# 2312_SchemaBloc.net
KiCad netlist of a schematic drawn in Altium Designer
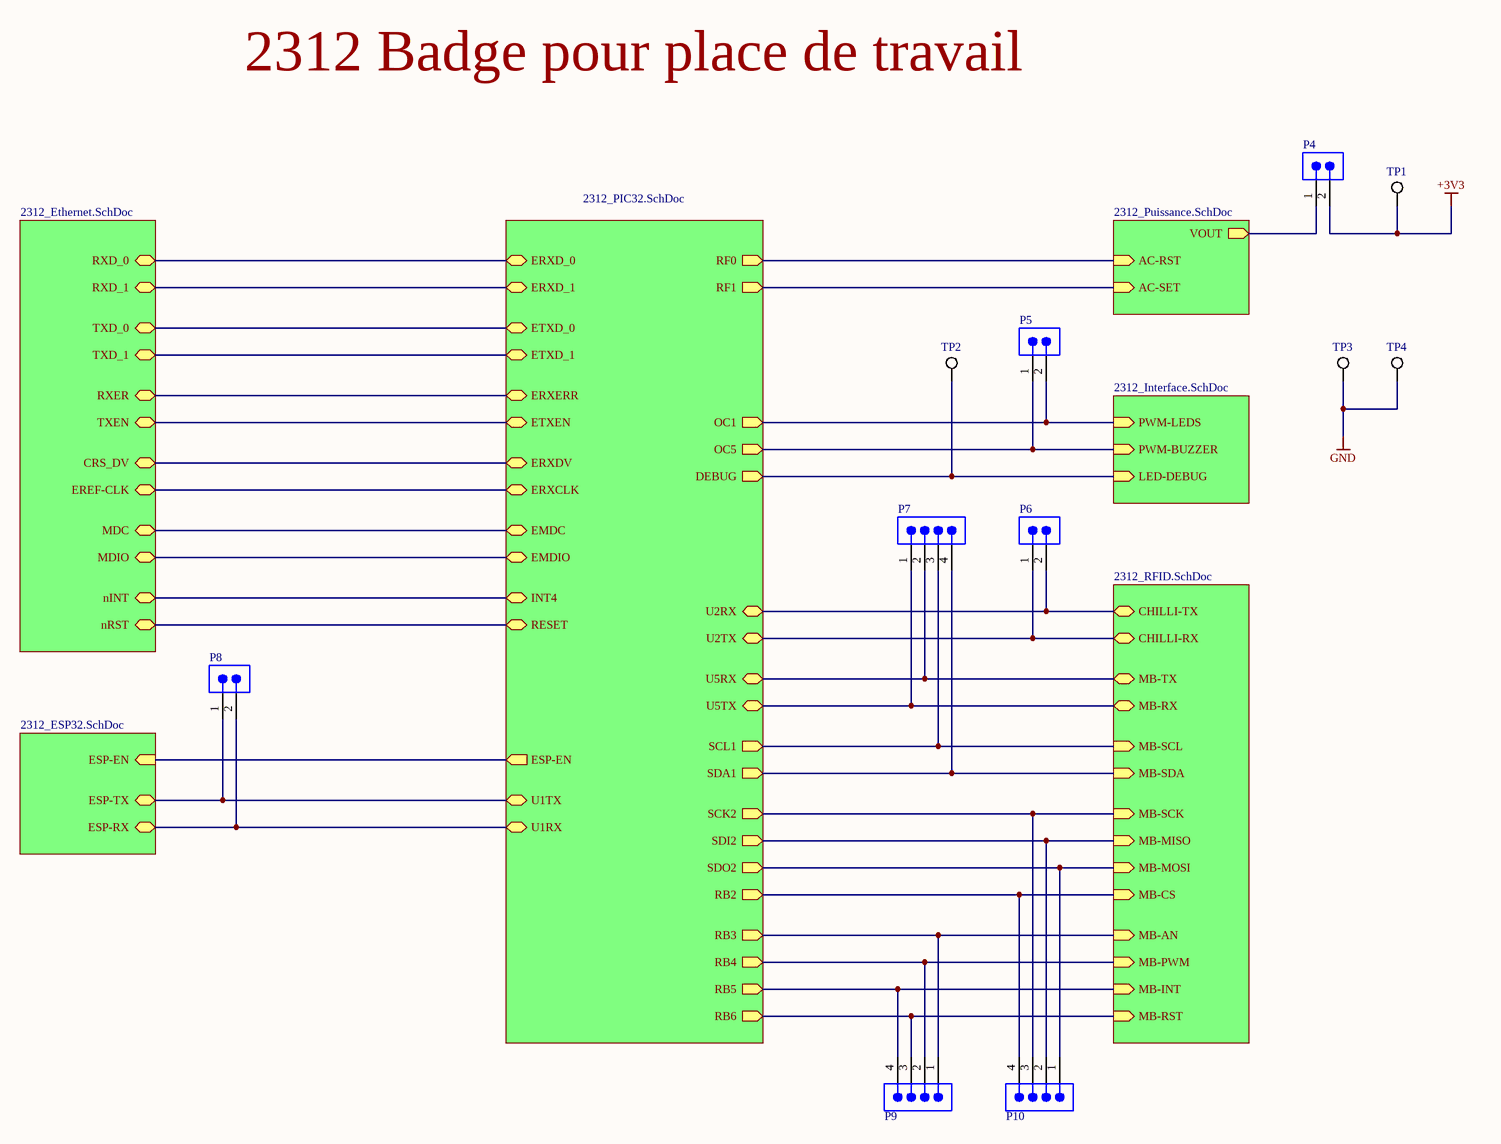
[diagram p0: 2312_SchemaBloc.SchDoc]

(export (version "E")
  (design (tool "Eeschema 10.0.6"))
  (components
    (comp (ref "P4")
      (value "61300211121")
      (footprint "61300211121")
      (description "WR-PHD Pin Header, THT, Vertical, pitch 2.54mm, 1 Row, 2P")
      (fields (field (name "MANUFACTURER") "Wurth Elektronik"))
      (libsource (lib "WR-PHD") (part "61300211121"))
    )
    (comp (ref "P5")
      (value "61300211121")
      (footprint "61300211121")
      (description "WR-PHD Pin Header, THT, Vertical, pitch 2.54mm, 1 Row, 2P")
      (fields (field (name "MANUFACTURER") "Wurth Elektronik"))
      (libsource (lib "WR-PHD") (part "61300211121"))
    )
    (comp (ref "P6")
      (value "61300211121")
      (footprint "61300211121")
      (description "WR-PHD Pin Header, THT, Vertical, pitch 2.54mm, 1 Row, 2P")
      (fields (field (name "MANUFACTURER") "Wurth Elektronik"))
      (libsource (lib "WR-PHD") (part "61300211121"))
    )
    (comp (ref "P7")
      (value "61300411121")
      (footprint "61300411121")
      (description "WR-PHD Pin Header, THT, Vertical, pitch 2.54mm, 1 Row, 4P")
      (fields (field (name "MANUFACTURER") "Wurth Elektronik"))
      (libsource (lib "WR-PHD") (part "61300411121"))
    )
    (comp (ref "P8")
      (value "61300211121")
      (footprint "61300211121")
      (description "WR-PHD Pin Header, THT, Vertical, pitch 2.54mm, 1 Row, 2P")
      (fields (field (name "MANUFACTURER") "Wurth Elektronik"))
      (libsource (lib "WR-PHD") (part "61300211121"))
    )
    (comp (ref "P9")
      (value "61300411121")
      (footprint "61300411121")
      (description "WR-PHD Pin Header, THT, Vertical, pitch 2.54mm, 1 Row, 4P")
      (fields (field (name "MANUFACTURER") "Wurth Elektronik"))
      (libsource (lib "WR-PHD") (part "61300411121"))
    )
    (comp (ref "P10")
      (value "61300411121")
      (footprint "61300411121")
      (description "WR-PHD Pin Header, THT, Vertical, pitch 2.54mm, 1 Row, 4P")
      (fields (field (name "MANUFACTURER") "Wurth Elektronik"))
      (libsource (lib "WR-PHD") (part "61300411121"))
    )
    (comp (ref "TP1")
      (value "5019")
      (footprint "KSTN-5019_V")
      (description "Test Point, 1 Position SMD, RoHS, Tape and Reel")
      (libsource (lib "Altium Content Vault") (part "TESTPOINT_WHITE"))
    )
    (comp (ref "TP2")
      (value "5019")
      (footprint "KSTN-5019_V")
      (description "Test Point, 1 Position SMD, RoHS, Tape and Reel")
      (libsource (lib "Altium Content Vault") (part "TESTPOINT_WHITE"))
    )
    (comp (ref "TP3")
      (value "5019")
      (footprint "KSTN-5019_V")
      (description "Test Point, 1 Position SMD, RoHS, Tape and Reel")
      (libsource (lib "Altium Content Vault") (part "TESTPOINT_WHITE"))
    )
    (comp (ref "TP4")
      (value "5019")
      (footprint "KSTN-5019_V")
      (description "Test Point, 1 Position SMD, RoHS, Tape and Reel")
      (libsource (lib "Altium Content Vault") (part "TESTPOINT_WHITE"))
    )
  )
  (nets
    (net (code "1") (name "+3V3") (class "Default")
      (node (ref "P4") (pin "2") (pinfunction "2_2") (pintype "passive"))
      (node (ref "TP1") (pin "1") (pinfunction "1_1") (pintype "passive"))
    )
    (net (code "2") (name "/CHILLI-RX") (class "Default")
      (node (ref "P6") (pin "1") (pinfunction "1_1") (pintype "passive"))
    )
    (net (code "3") (name "/CHILLI-TX") (class "Default")
      (node (ref "P6") (pin "2") (pinfunction "2_2") (pintype "passive"))
    )
    (net (code "5") (name "/DEBUG") (class "Default")
      (node (ref "TP2") (pin "1") (pinfunction "1_1") (pintype "passive"))
    )
    (net (code "13") (name "/ESP-RX") (class "Default")
      (node (ref "P8") (pin "2") (pinfunction "2_2") (pintype "passive"))
    )
    (net (code "14") (name "/ESP-TX") (class "Default")
      (node (ref "P8") (pin "1") (pinfunction "1_1") (pintype "passive"))
    )
    (net (code "19") (name "/MB-RX") (class "Default")
      (node (ref "P7") (pin "1") (pinfunction "1_1") (pintype "passive"))
    )
    (net (code "20") (name "/MB-TX") (class "Default")
      (node (ref "P7") (pin "2") (pinfunction "2_2") (pintype "passive"))
    )
    (net (code "21") (name "/OC1") (class "Default")
      (node (ref "P5") (pin "2") (pinfunction "2_2") (pintype "passive"))
    )
    (net (code "22") (name "/OC5") (class "Default")
      (node (ref "P5") (pin "1") (pinfunction "1_1") (pintype "passive"))
    )
    (net (code "23") (name "/RB2") (class "Default")
      (node (ref "P10") (pin "4") (pinfunction "4_4") (pintype "passive"))
    )
    (net (code "24") (name "/RB3") (class "Default")
      (node (ref "P9") (pin "1") (pinfunction "1_1") (pintype "passive"))
    )
    (net (code "25") (name "/RB4") (class "Default")
      (node (ref "P9") (pin "2") (pinfunction "2_2") (pintype "passive"))
    )
    (net (code "26") (name "/RB5") (class "Default")
      (node (ref "P9") (pin "4") (pinfunction "4_4") (pintype "passive"))
    )
    (net (code "27") (name "/RB6") (class "Default")
      (node (ref "P9") (pin "3") (pinfunction "3_3") (pintype "passive"))
    )
    (net (code "31") (name "/SCK2") (class "Default")
      (node (ref "P10") (pin "3") (pinfunction "3_3") (pintype "passive"))
    )
    (net (code "32") (name "/SCL1") (class "Default")
      (node (ref "P7") (pin "3") (pinfunction "3_3") (pintype "passive"))
    )
    (net (code "33") (name "/SDA1") (class "Default")
      (node (ref "P7") (pin "4") (pinfunction "4_4") (pintype "passive"))
    )
    (net (code "34") (name "/SDI2") (class "Default")
      (node (ref "P10") (pin "2") (pinfunction "2_2") (pintype "passive"))
    )
    (net (code "35") (name "/SDO2") (class "Default")
      (node (ref "P10") (pin "1") (pinfunction "1_1") (pintype "passive"))
    )
    (net (code "36") (name "/VOUT") (class "Default")
      (node (ref "P4") (pin "1") (pinfunction "1_1") (pintype "passive"))
    )
    (net (code "37") (name "GND") (class "Default")
      (node (ref "TP3") (pin "1") (pinfunction "1_1") (pintype "passive"))
      (node (ref "TP4") (pin "1") (pinfunction "1_1") (pintype "passive"))
    )
  )
)
